# main.net
KiCad netlist of a schematic drawn in Altium Designer
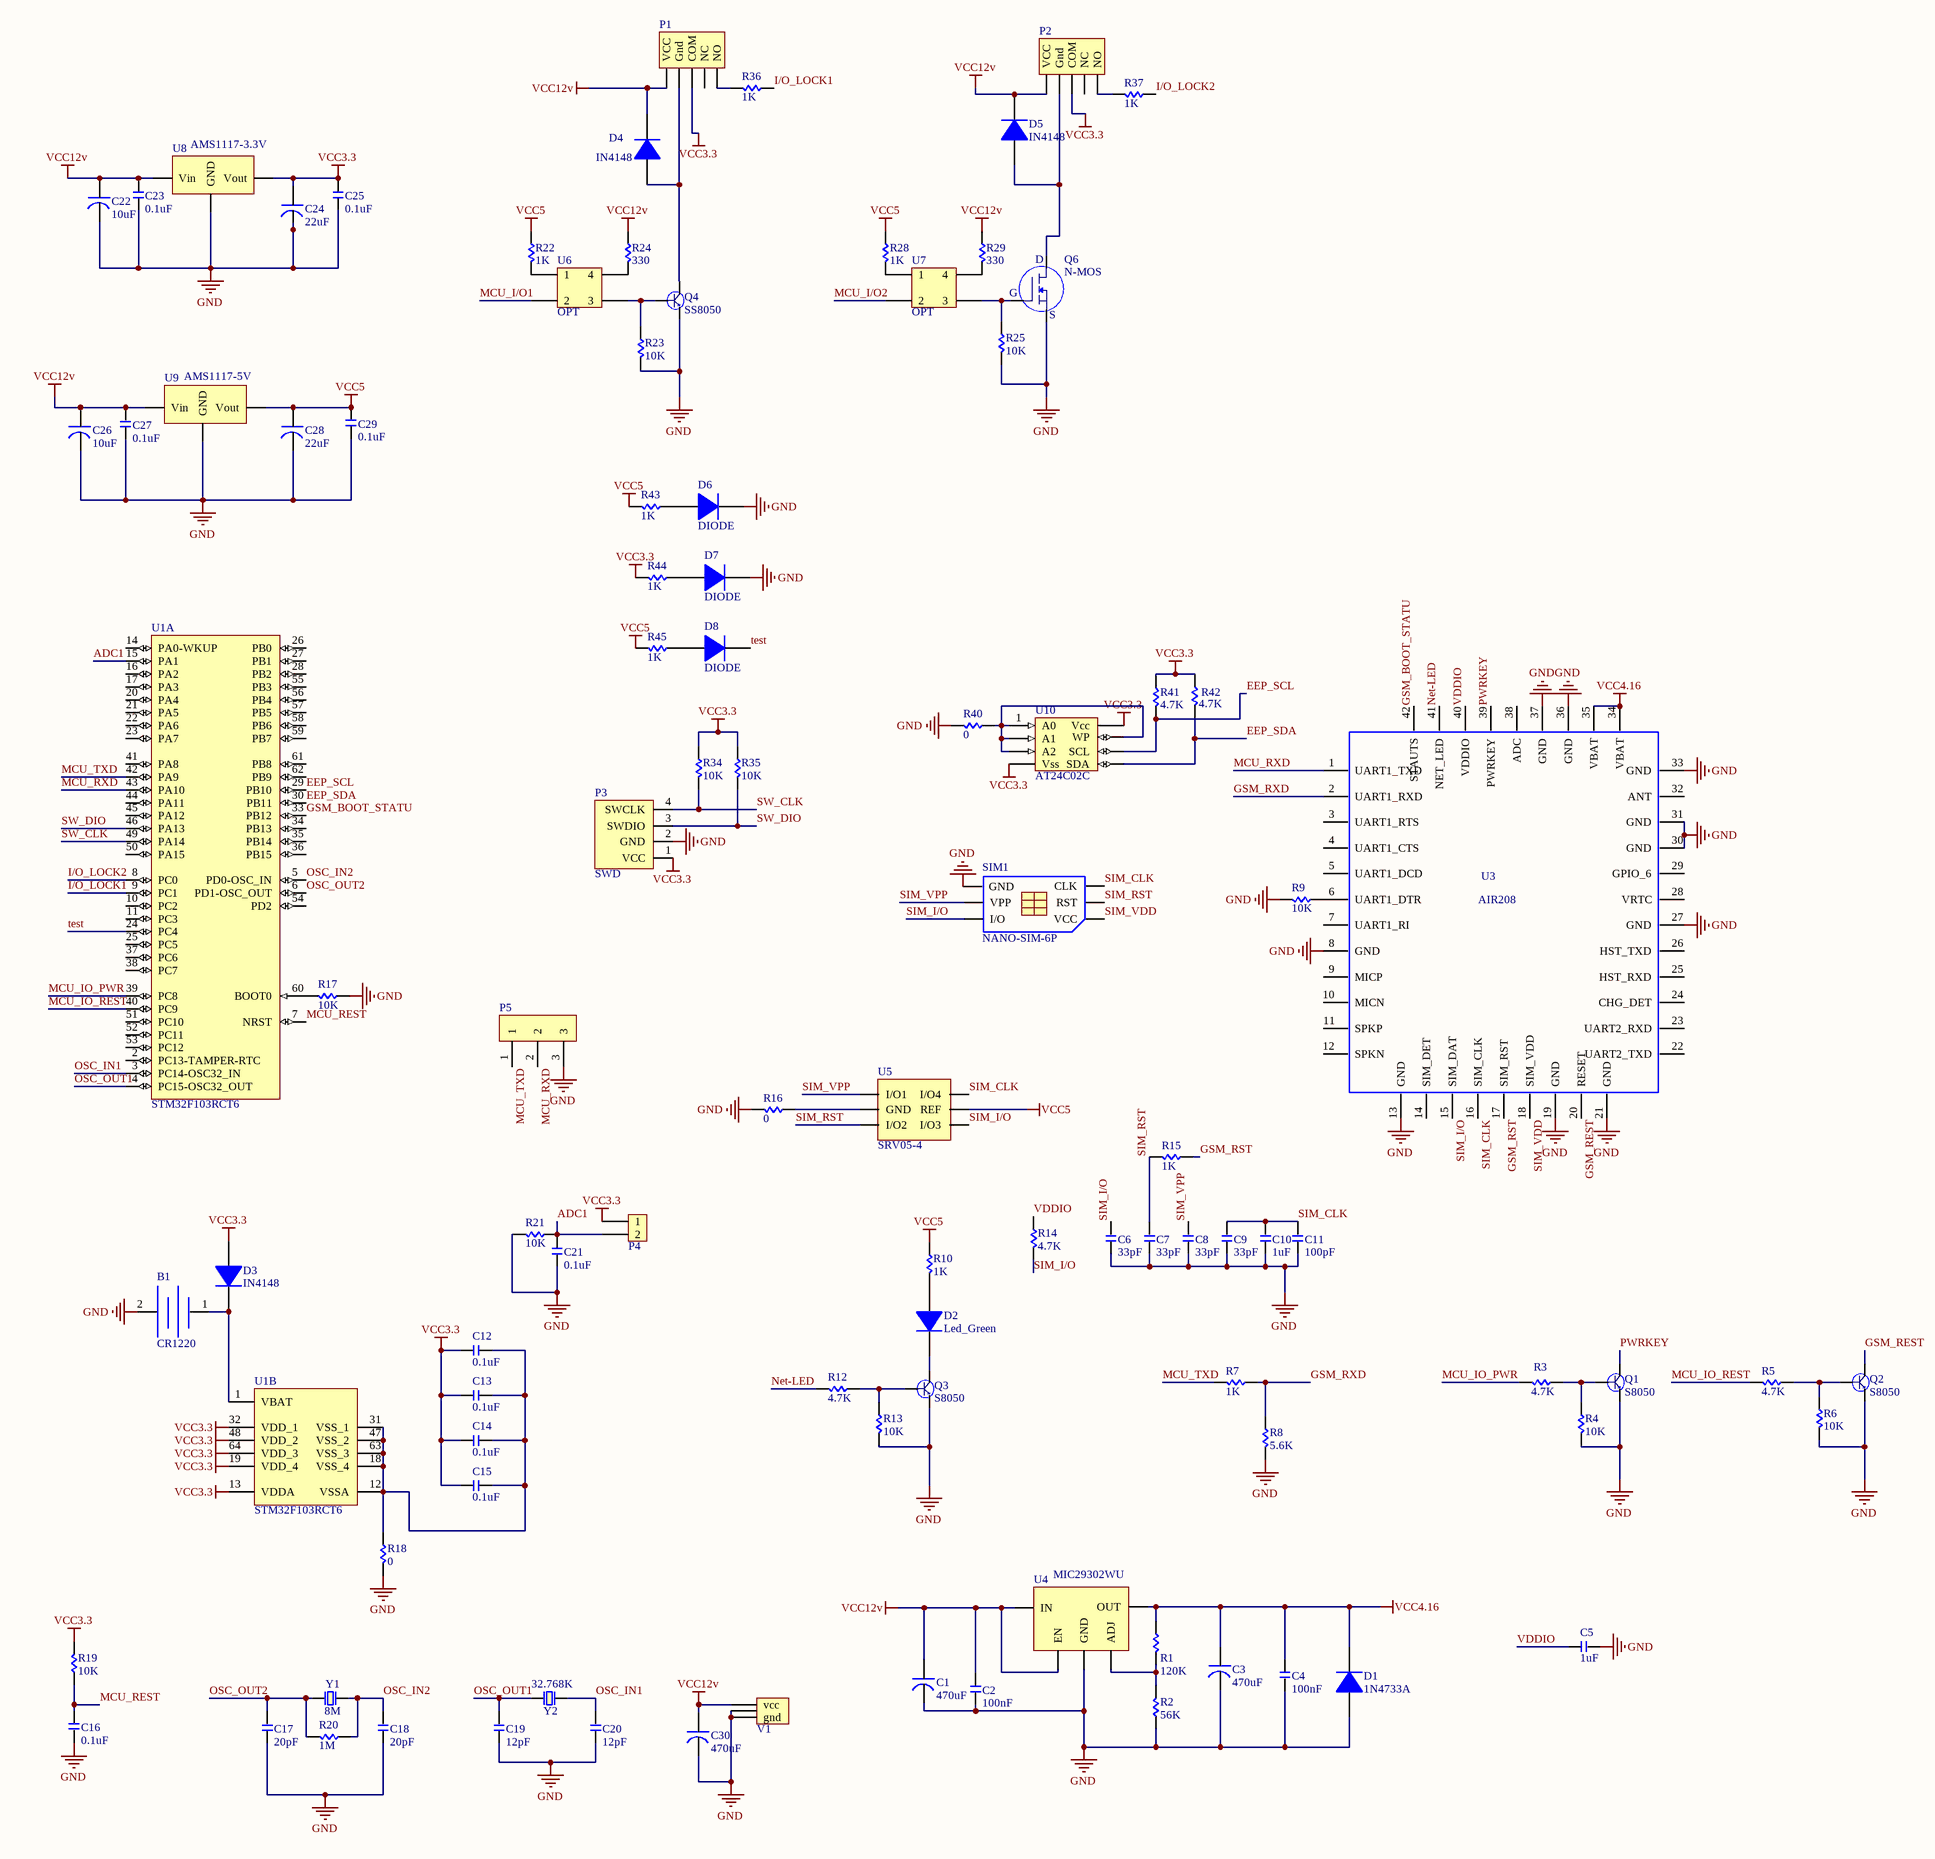
[diagram p0: main.SchDoc]

(export (version "E")
  (design (tool "Eeschema 10.0.6"))
  (components
    (comp (ref "B1") (value "CR1220") (footprint "CR1220") (libsource (lib "dev") (part "BAT")))
    (comp (ref "C1") (value "470uF") (footprint "10mmx10mm+") (libsource (lib "dev") (part "Cap_Elec")))
    (comp (ref "C2") (value "100nF") (footprint "0805") (libsource (lib "dev") (part "Cap")))
    (comp (ref "C3") (value "470uF") (footprint "10mmx10mm+") (libsource (lib "dev") (part "Cap_Elec")))
    (comp (ref "C4") (value "100nF") (footprint "0805") (libsource (lib "dev") (part "Cap")))
    (comp (ref "C5") (value "1uF") (footprint "0805") (libsource (lib "dev") (part "Cap")))
    (comp (ref "C6") (value "33pF") (footprint "0805") (libsource (lib "dev") (part "Cap")))
    (comp (ref "C7") (value "33pF") (footprint "0805") (libsource (lib "dev") (part "Cap")))
    (comp (ref "C8") (value "33pF") (footprint "0805") (libsource (lib "dev") (part "Cap")))
    (comp (ref "C9") (value "33pF") (footprint "0805") (libsource (lib "dev") (part "Cap")))
    (comp (ref "C10") (value "1uF") (footprint "0805") (libsource (lib "dev") (part "Cap")))
    (comp (ref "C11") (value "100pF") (footprint "0805") (libsource (lib "dev") (part "Cap")))
    (comp (ref "C12") (value "0.1uF") (footprint "0805") (libsource (lib "dev") (part "Cap")))
    (comp (ref "C13") (value "0.1uF") (footprint "0805") (libsource (lib "dev") (part "Cap")))
    (comp (ref "C14") (value "0.1uF") (footprint "0805") (libsource (lib "dev") (part "Cap")))
    (comp (ref "C15") (value "0.1uF") (footprint "0805") (libsource (lib "dev") (part "Cap")))
    (comp (ref "C16") (value "0.1uF") (footprint "0805") (libsource (lib "dev") (part "Cap")))
    (comp (ref "C17") (value "20pF") (footprint "0805") (libsource (lib "dev") (part "Cap")))
    (comp (ref "C18") (value "20pF") (footprint "0805") (libsource (lib "dev") (part "Cap")))
    (comp (ref "C19") (value "12pF") (footprint "0805") (libsource (lib "dev") (part "Cap")))
    (comp (ref "C20") (value "12pF") (footprint "0805") (libsource (lib "dev") (part "Cap")))
    (comp (ref "C21") (value "0.1uF") (footprint "0805") (libsource (lib "dev") (part "Cap")))
    (comp (ref "C22") (value "10uF") (footprint "1206") (libsource (lib "dev") (part "Cap_Elec")))
    (comp (ref "C23") (value "0.1uF") (footprint "0805") (libsource (lib "dev") (part "Cap")))
    (comp (ref "C24") (value "22uF") (footprint "1206") (libsource (lib "dev") (part "Cap_Elec")))
    (comp (ref "C25") (value "0.1uF") (footprint "0805") (libsource (lib "dev") (part "Cap")))
    (comp (ref "C26") (value "10uF") (footprint "1206") (libsource (lib "dev") (part "Cap_Elec")))
    (comp (ref "C27") (value "0.1uF") (footprint "0805") (libsource (lib "dev") (part "Cap")))
    (comp (ref "C28") (value "22uF") (footprint "1206") (libsource (lib "dev") (part "Cap_Elec")))
    (comp (ref "C29") (value "0.1uF") (footprint "0805") (libsource (lib "dev") (part "Cap")))
    (comp (ref "C30") (value "470uF") (footprint "DIP2_8.3x3.1") (libsource (lib "dev") (part "Cap_Elec")))
    (comp (ref "D1") (value "1N4733A") (footprint "Dip-6mm") (libsource (lib "dev") (part "DIODE")))
    (comp (ref "D2") (value "Led_Green") (footprint "0603") (libsource (lib "dev") (part "DIODE")))
    (comp (ref "D3") (value "IN4148") (footprint "1206") (libsource (lib "dev") (part "DIODE")))
    (comp (ref "D4") (value "IN4148") (footprint "1206") (libsource (lib "dev") (part "DIODE")))
    (comp (ref "D5") (value "IN4148") (footprint "1206") (libsource (lib "dev") (part "DIODE")))
    (comp (ref "D6") (value "DIODE") (footprint "0603") (libsource (lib "dev") (part "DIODE")))
    (comp (ref "D7") (value "DIODE") (footprint "0603") (libsource (lib "dev") (part "DIODE")))
    (comp (ref "D8") (value "DIODE") (footprint "0603") (libsource (lib "dev") (part "DIODE")))
    (comp (ref "P1") (value "Ele_lock_Pin") (footprint "Pin5") (libsource (lib "dev") (part "Ele_lock_Pin")))
    (comp (ref "P2") (value "Ele_lock_Pin") (footprint "Pin5") (libsource (lib "dev") (part "Ele_lock_Pin")))
    (comp (ref "P3") (value "SWD") (footprint "PIN4") (libsource (lib "dev") (part "SWD")))
    (comp (ref "P4") (value "Pin2") (footprint "XH2.54_2") (libsource (lib "dev") (part "Pin2")))
    (comp (ref "P5") (value "pin3") (footprint "PIN3") (libsource (lib "dev") (part "pin3")))
    (comp (ref "Q1") (value "S8050") (footprint "sot-23") (libsource (lib "dev") (part "Npn-Sot-23")))
    (comp (ref "Q2") (value "S8050") (footprint "sot-23") (libsource (lib "dev") (part "Npn-Sot-23")))
    (comp (ref "Q3") (value "S8050") (footprint "sot-23") (libsource (lib "dev") (part "Npn-Sot-23")))
    (comp (ref "Q4") (value "SS8050") (footprint "sot-23") (libsource (lib "dev") (part "Npn-Sot-23")))
    (comp (ref "Q6") (value "N-MOS") (footprint "SOT-23-3") (libsource (lib "dev") (part "N-MOS")))
    (comp (ref "R1") (value "120K") (footprint "0805") (libsource (lib "dev") (part "Res")))
    (comp (ref "R2") (value "56K") (footprint "0805") (libsource (lib "dev") (part "Res")))
    (comp (ref "R3") (value "4.7K") (footprint "0805") (libsource (lib "dev") (part "Res")))
    (comp (ref "R4") (value "10K") (footprint "0805") (libsource (lib "dev") (part "Res")))
    (comp (ref "R5") (value "4.7K") (footprint "0805") (libsource (lib "dev") (part "Res")))
    (comp (ref "R6") (value "10K") (footprint "0805") (libsource (lib "dev") (part "Res")))
    (comp (ref "R7") (value "1K") (footprint "0805") (libsource (lib "dev") (part "Res")))
    (comp (ref "R8") (value "5.6K") (footprint "0805") (libsource (lib "dev") (part "Res")))
    (comp (ref "R9") (value "10K") (footprint "0805") (libsource (lib "dev") (part "Res")))
    (comp (ref "R10") (value "1K") (footprint "0805") (libsource (lib "dev") (part "Res")))
    (comp (ref "R12") (value "4.7K") (footprint "0805") (libsource (lib "dev") (part "Res")))
    (comp (ref "R13") (value "10K") (footprint "0805") (libsource (lib "dev") (part "Res")))
    (comp (ref "R14") (value "4.7K") (footprint "0805") (libsource (lib "dev") (part "Res")))
    (comp (ref "R15") (value "1K") (footprint "0805") (libsource (lib "dev") (part "Res")))
    (comp (ref "R16") (value "0") (footprint "0603") (libsource (lib "dev") (part "Res")))
    (comp (ref "R17") (value "10K") (footprint "0805") (libsource (lib "dev") (part "Res")))
    (comp (ref "R18") (value "0") (footprint "0603") (libsource (lib "dev") (part "Res")))
    (comp (ref "R19") (value "10K") (footprint "0805") (libsource (lib "dev") (part "Res")))
    (comp (ref "R20") (value "1M") (footprint "0805") (libsource (lib "dev") (part "Res")))
    (comp (ref "R21") (value "10K") (footprint "0805") (libsource (lib "dev") (part "Res")))
    (comp (ref "R22") (value "1K") (footprint "0805") (libsource (lib "dev") (part "Res")))
    (comp (ref "R23") (value "10K") (footprint "0805") (libsource (lib "dev") (part "Res")))
    (comp (ref "R24") (value "330") (footprint "0805") (libsource (lib "dev") (part "Res")))
    (comp (ref "R25") (value "10K") (footprint "0805") (libsource (lib "dev") (part "Res")))
    (comp (ref "R28") (value "1K") (footprint "0805") (libsource (lib "dev") (part "Res")))
    (comp (ref "R29") (value "330") (footprint "0805") (libsource (lib "dev") (part "Res")))
    (comp (ref "R34") (value "10K") (footprint "0805") (libsource (lib "dev") (part "Res")))
    (comp (ref "R35") (value "10K") (footprint "0805") (libsource (lib "dev") (part "Res")))
    (comp (ref "R36") (value "1K") (footprint "0805") (libsource (lib "dev") (part "Res")))
    (comp (ref "R37") (value "1K") (footprint "0805") (libsource (lib "dev") (part "Res")))
    (comp (ref "R40") (value "0") (footprint "0603") (libsource (lib "dev") (part "Res")))
    (comp (ref "R41") (value "4.7K") (footprint "0603") (libsource (lib "dev") (part "Res")))
    (comp (ref "R42") (value "4.7K") (footprint "0603") (libsource (lib "dev") (part "Res")))
    (comp (ref "R43") (value "1K") (footprint "0603") (libsource (lib "dev") (part "Res")))
    (comp (ref "R44") (value "1K") (footprint "0603") (libsource (lib "dev") (part "Res")))
    (comp (ref "R45") (value "1K") (footprint "0603") (libsource (lib "dev") (part "Res")))
    (comp (ref "SIM1")
      (value "NANO-SIM-6P")
      (footprint "NANO-SIM-6P")
      (libsource (lib "dev") (part "NANO-SIM-6P"))
    )
    (comp (ref "U1")
      (value "STM32F103RCT6")
      (footprint "STM-LQFP64_M")
      (libsource (lib "STMicroelectronics STM32 F1") (part "STM32F103RCT6"))
    )
    (comp (ref "U3") (value "AIR208") (footprint "Air208") (libsource (lib "AIR208") (part "AIR208")))
    (comp (ref "U4") (value "MIC29302WU") (footprint "TO-263-5") (libsource (lib "dev") (part "MIC29302WU")))
    (comp (ref "U5") (value "SRV05-4") (footprint "Sot-23-6") (libsource (lib "dev") (part "SRV05-4")))
    (comp (ref "U6") (value "OPT") (footprint "SOP4") (libsource (lib "dev") (part "OPT")))
    (comp (ref "U7") (value "OPT") (footprint "SOP4") (libsource (lib "dev") (part "OPT")))
    (comp (ref "U8")
      (value "AMS1117-3.3V")
      (footprint "SOT-223")
      (libsource (lib "dev") (part "AMS1117-3.3V"))
    )
    (comp (ref "U9") (value "AMS1117-5V") (footprint "SOT-223") (libsource (lib "dev") (part "AMS1117-3.3V")))
    (comp (ref "U10") (value "AT24C02C") (footprint "SOP8") (libsource (lib "dev") (part "AT24C02C")))
    (comp (ref "V1")
      (value "POWER_PIN")
      (footprint "POWER_PIN_PCB")
      (libsource (lib "dev") (part "POWER_PIN"))
    )
    (comp (ref "Y1") (value "8M") (footprint "crystal") (libsource (lib "dev") (part "crystal")))
    (comp (ref "Y2") (value "32.768K") (footprint "PIN1.1") (libsource (lib "dev") (part "crystal")))
  )
  (nets
    (net (code "1") (name "/ADC1") (class "Default")
      (node (ref "C21") (pin "2") (pinfunction "2_2") (pintype "passive"))
      (node (ref "P4") (pin "2") (pinfunction "2_2") (pintype "passive"))
      (node (ref "R21") (pin "2") (pinfunction "2_2") (pintype "passive"))
      (node (ref "U1") (pin "15") (pinfunction "PA1_15") (pintype "bidirectional"))
    )
    (net (code "2") (name "/EEP_SCL") (class "Default")
      (node (ref "R41") (pin "1") (pinfunction "1_1") (pintype "passive"))
      (node (ref "U1") (pin "29") (pinfunction "PB10_29") (pintype "bidirectional"))
      (node (ref "U10") (pin "6") (pinfunction "SCL_6") (pintype "bidirectional"))
    )
    (net (code "3") (name "/EEP_SDA") (class "Default")
      (node (ref "R42") (pin "1") (pinfunction "1_1") (pintype "passive"))
      (node (ref "U1") (pin "30") (pinfunction "PB11_30") (pintype "bidirectional"))
      (node (ref "U10") (pin "5") (pinfunction "SDA_5") (pintype "bidirectional"))
    )
    (net (code "4") (name "/GSM_BOOT_STATU") (class "Default")
      (node (ref "U1") (pin "33") (pinfunction "PB12_33") (pintype "bidirectional"))
      (node (ref "U3") (pin "42") (pinfunction "STAUTS_42") (pintype "passive"))
    )
    (net (code "5") (name "/GSM_REST") (class "Default")
      (node (ref "Q2") (pin "3") (pinfunction "3_3") (pintype "passive"))
      (node (ref "U3") (pin "20") (pinfunction "RESET_20") (pintype "passive"))
    )
    (net (code "6") (name "/GSM_RST") (class "Default")
      (node (ref "R15") (pin "2") (pinfunction "2_2") (pintype "passive"))
      (node (ref "U3") (pin "17") (pinfunction "SIM_RST_17") (pintype "passive"))
    )
    (net (code "7") (name "/GSM_RXD") (class "Default")
      (node (ref "R7") (pin "2") (pinfunction "2_2") (pintype "passive"))
      (node (ref "R8") (pin "2") (pinfunction "2_2") (pintype "passive"))
      (node (ref "U3") (pin "2") (pinfunction "UART1_RXD_2") (pintype "passive"))
    )
    (net (code "8") (name "/I{slash}O_LOCK1") (class "Default")
      (node (ref "R36") (pin "2") (pinfunction "2_2") (pintype "passive"))
      (node (ref "U1") (pin "9") (pinfunction "PC1_9") (pintype "bidirectional"))
    )
    (net (code "9") (name "/I{slash}O_LOCK2") (class "Default")
      (node (ref "R37") (pin "2") (pinfunction "2_2") (pintype "passive"))
      (node (ref "U1") (pin "8") (pinfunction "PC0_8") (pintype "bidirectional"))
    )
    (net (code "10") (name "/MCU_IO_PWR") (class "Default")
      (node (ref "R3") (pin "1") (pinfunction "1_1") (pintype "passive"))
      (node (ref "U1") (pin "39") (pinfunction "PC8_39") (pintype "bidirectional"))
    )
    (net (code "11") (name "/MCU_IO_REST") (class "Default")
      (node (ref "R5") (pin "1") (pinfunction "1_1") (pintype "passive"))
      (node (ref "U1") (pin "40") (pinfunction "PC9_40") (pintype "bidirectional"))
    )
    (net (code "12") (name "/MCU_I{slash}O1") (class "Default")
      (node (ref "U6") (pin "2") (pinfunction "2_2") (pintype "passive"))
    )
    (net (code "13") (name "/MCU_I{slash}O2") (class "Default")
      (node (ref "U7") (pin "2") (pinfunction "2_2") (pintype "passive"))
    )
    (net (code "14") (name "/MCU_REST") (class "Default")
      (node (ref "C16") (pin "1") (pinfunction "1_1") (pintype "passive"))
      (node (ref "R19") (pin "2") (pinfunction "2_2") (pintype "passive"))
      (node (ref "U1") (pin "7") (pinfunction "NRST_7") (pintype "bidirectional"))
    )
    (net (code "15") (name "/MCU_RXD") (class "Default")
      (node (ref "P5") (pin "2") (pinfunction "2_2") (pintype "passive"))
      (node (ref "U1") (pin "43") (pinfunction "PA10_43") (pintype "bidirectional"))
      (node (ref "U3") (pin "1") (pinfunction "UART1_TXD_1") (pintype "passive"))
    )
    (net (code "16") (name "/MCU_TXD") (class "Default")
      (node (ref "P5") (pin "1") (pinfunction "1_1") (pintype "passive"))
      (node (ref "R7") (pin "1") (pinfunction "1_1") (pintype "passive"))
      (node (ref "U1") (pin "42") (pinfunction "PA9_42") (pintype "bidirectional"))
    )
    (net (code "17") (name "/Net-LED") (class "Default")
      (node (ref "R12") (pin "1") (pinfunction "1_1") (pintype "passive"))
      (node (ref "U3") (pin "41") (pinfunction "NET_LED_41") (pintype "passive"))
    )
    (net (code "18") (name "/OSC_IN1") (class "Default")
      (node (ref "C20") (pin "2") (pinfunction "2_2") (pintype "passive"))
      (node (ref "U1") (pin "3") (pinfunction "PC14-OSC32_IN_3") (pintype "bidirectional"))
      (node (ref "Y2") (pin "2") (pinfunction "2_2") (pintype "passive"))
    )
    (net (code "19") (name "/OSC_IN2") (class "Default")
      (node (ref "C18") (pin "2") (pinfunction "2_2") (pintype "passive"))
      (node (ref "R20") (pin "2") (pinfunction "2_2") (pintype "passive"))
      (node (ref "U1") (pin "5") (pinfunction "PD0-OSC_IN_5") (pintype "bidirectional"))
      (node (ref "Y1") (pin "2") (pinfunction "2_2") (pintype "passive"))
    )
    (net (code "20") (name "/OSC_OUT1") (class "Default")
      (node (ref "C19") (pin "2") (pinfunction "2_2") (pintype "passive"))
      (node (ref "U1") (pin "4") (pinfunction "PC15-OSC32_OUT_4") (pintype "bidirectional"))
      (node (ref "Y2") (pin "1") (pinfunction "1_1") (pintype "passive"))
    )
    (net (code "21") (name "/OSC_OUT2") (class "Default")
      (node (ref "C17") (pin "2") (pinfunction "2_2") (pintype "passive"))
      (node (ref "R20") (pin "1") (pinfunction "1_1") (pintype "passive"))
      (node (ref "U1") (pin "6") (pinfunction "PD1-OSC_OUT_6") (pintype "bidirectional"))
      (node (ref "Y1") (pin "1") (pinfunction "1_1") (pintype "passive"))
    )
    (net (code "22") (name "/PWRKEY") (class "Default")
      (node (ref "Q1") (pin "3") (pinfunction "3_3") (pintype "passive"))
      (node (ref "U3") (pin "39") (pinfunction "PWRKEY_39") (pintype "passive"))
    )
    (net (code "23") (name "/SIM_CLK") (class "Default")
      (node (ref "C10") (pin "2") (pinfunction "2_2") (pintype "passive"))
      (node (ref "C11") (pin "2") (pinfunction "2_2") (pintype "passive"))
      (node (ref "C9") (pin "2") (pinfunction "2_2") (pintype "passive"))
      (node (ref "SIM1") (pin "3") (pinfunction "CLK_3") (pintype "passive"))
      (node (ref "U3") (pin "16") (pinfunction "SIM_CLK_16") (pintype "passive"))
      (node (ref "U5") (pin "6") (pinfunction "I/O4_6") (pintype "passive"))
    )
    (net (code "24") (name "/SIM_I{slash}O") (class "Default")
      (node (ref "C6") (pin "2") (pinfunction "2_2") (pintype "passive"))
      (node (ref "R14") (pin "1") (pinfunction "1_1") (pintype "passive"))
      (node (ref "SIM1") (pin "7") (pinfunction "I/O_7") (pintype "passive"))
      (node (ref "U3") (pin "15") (pinfunction "SIM_DAT_15") (pintype "passive"))
      (node (ref "U5") (pin "4") (pinfunction "I/O3_4") (pintype "passive"))
    )
    (net (code "25") (name "/SIM_RST") (class "Default")
      (node (ref "C7") (pin "2") (pinfunction "2_2") (pintype "passive"))
      (node (ref "R15") (pin "1") (pinfunction "1_1") (pintype "passive"))
      (node (ref "SIM1") (pin "2") (pinfunction "RST_2") (pintype "passive"))
      (node (ref "U5") (pin "3") (pinfunction "I/O2_3") (pintype "passive"))
    )
    (net (code "26") (name "/SIM_VDD") (class "Default")
      (node (ref "SIM1") (pin "1") (pinfunction "VCC_1") (pintype "passive"))
      (node (ref "U3") (pin "18") (pinfunction "SIM_VDD_18") (pintype "passive"))
    )
    (net (code "27") (name "/SIM_VPP") (class "Default")
      (node (ref "C8") (pin "2") (pinfunction "2_2") (pintype "passive"))
      (node (ref "SIM1") (pin "6") (pinfunction "VPP_6") (pintype "passive"))
      (node (ref "U5") (pin "1") (pinfunction "I/O1_1") (pintype "passive"))
    )
    (net (code "28") (name "/SW_CLK") (class "Default")
      (node (ref "P3") (pin "4") (pinfunction "SWCLK_4") (pintype "passive"))
      (node (ref "R34") (pin "1") (pinfunction "1_1") (pintype "passive"))
      (node (ref "U1") (pin "49") (pinfunction "PA14_49") (pintype "bidirectional"))
    )
    (net (code "29") (name "/SW_DIO") (class "Default")
      (node (ref "P3") (pin "3") (pinfunction "SWDIO_3") (pintype "passive"))
      (node (ref "R35") (pin "1") (pinfunction "1_1") (pintype "passive"))
      (node (ref "U1") (pin "46") (pinfunction "PA13_46") (pintype "bidirectional"))
    )
    (net (code "30") (name "/VDDIO") (class "Default")
      (node (ref "C5") (pin "1") (pinfunction "1_1") (pintype "passive"))
      (node (ref "R14") (pin "2") (pinfunction "2_2") (pintype "passive"))
      (node (ref "U3") (pin "40") (pinfunction "VDDIO_40") (pintype "passive"))
    )
    (net (code "31") (name "/test") (class "Default")
      (node (ref "D8") (pin "2") (pinfunction "2_2") (pintype "passive"))
      (node (ref "U1") (pin "24") (pinfunction "PC4_24") (pintype "bidirectional"))
    )
    (net (code "32") (name "GND") (class "Default")
      (node (ref "B1") (pin "2") (pinfunction "2_2") (pintype "passive"))
      (node (ref "C1") (pin "2") (pinfunction "2_2") (pintype "passive"))
      (node (ref "C10") (pin "1") (pinfunction "1_1") (pintype "passive"))
      (node (ref "C11") (pin "1") (pinfunction "1_1") (pintype "passive"))
      (node (ref "C16") (pin "2") (pinfunction "2_2") (pintype "passive"))
      (node (ref "C17") (pin "1") (pinfunction "1_1") (pintype "passive"))
      (node (ref "C18") (pin "1") (pinfunction "1_1") (pintype "passive"))
      (node (ref "C19") (pin "1") (pinfunction "1_1") (pintype "passive"))
      (node (ref "C2") (pin "1") (pinfunction "1_1") (pintype "passive"))
      (node (ref "C20") (pin "1") (pinfunction "1_1") (pintype "passive"))
      (node (ref "C21") (pin "1") (pinfunction "1_1") (pintype "passive"))
      (node (ref "C22") (pin "2") (pinfunction "2_2") (pintype "passive"))
      (node (ref "C23") (pin "1") (pinfunction "1_1") (pintype "passive"))
      (node (ref "C24") (pin "2") (pinfunction "2_2") (pintype "passive"))
      (node (ref "C25") (pin "1") (pinfunction "1_1") (pintype "passive"))
      (node (ref "C26") (pin "2") (pinfunction "2_2") (pintype "passive"))
      (node (ref "C27") (pin "1") (pinfunction "1_1") (pintype "passive"))
      (node (ref "C28") (pin "2") (pinfunction "2_2") (pintype "passive"))
      (node (ref "C29") (pin "2") (pinfunction "2_2") (pintype "passive"))
      (node (ref "C3") (pin "2") (pinfunction "2_2") (pintype "passive"))
      (node (ref "C30") (pin "2") (pinfunction "2_2") (pintype "passive"))
      (node (ref "C4") (pin "2") (pinfunction "2_2") (pintype "passive"))
      (node (ref "C5") (pin "2") (pinfunction "2_2") (pintype "passive"))
      (node (ref "C6") (pin "1") (pinfunction "1_1") (pintype "passive"))
      (node (ref "C7") (pin "1") (pinfunction "1_1") (pintype "passive"))
      (node (ref "C8") (pin "1") (pinfunction "1_1") (pintype "passive"))
      (node (ref "C9") (pin "1") (pinfunction "1_1") (pintype "passive"))
      (node (ref "D1") (pin "1") (pinfunction "1_1") (pintype "passive"))
      (node (ref "D6") (pin "2") (pinfunction "2_2") (pintype "passive"))
      (node (ref "D7") (pin "2") (pinfunction "2_2") (pintype "passive"))
      (node (ref "P3") (pin "2") (pinfunction "GND_2") (pintype "passive"))
      (node (ref "P5") (pin "3") (pinfunction "3_3") (pintype "passive"))
      (node (ref "Q1") (pin "2") (pinfunction "2_2") (pintype "passive"))
      (node (ref "Q2") (pin "2") (pinfunction "2_2") (pintype "passive"))
      (node (ref "Q3") (pin "2") (pinfunction "2_2") (pintype "passive"))
      (node (ref "Q4") (pin "2") (pinfunction "2_2") (pintype "passive"))
      (node (ref "Q6") (pin "2") (pinfunction "S_2") (pintype "passive"))
      (node (ref "R13") (pin "1") (pinfunction "1_1") (pintype "passive"))
      (node (ref "R16") (pin "1") (pinfunction "1_1") (pintype "passive"))
      (node (ref "R17") (pin "2") (pinfunction "2_2") (pintype "passive"))
      (node (ref "R18") (pin "1") (pinfunction "1_1") (pintype "passive"))
      (node (ref "R2") (pin "2") (pinfunction "2_2") (pintype "passive"))
      (node (ref "R21") (pin "1") (pinfunction "1_1") (pintype "passive"))
      (node (ref "R23") (pin "1") (pinfunction "1_1") (pintype "passive"))
      (node (ref "R25") (pin "1") (pinfunction "1_1") (pintype "passive"))
      (node (ref "R4") (pin "1") (pinfunction "1_1") (pintype "passive"))
      (node (ref "R40") (pin "1") (pinfunction "1_1") (pintype "passive"))
      (node (ref "R6") (pin "1") (pinfunction "1_1") (pintype "passive"))
      (node (ref "R8") (pin "1") (pinfunction "1_1") (pintype "passive"))
      (node (ref "R9") (pin "1") (pinfunction "1_1") (pintype "passive"))
      (node (ref "SIM1") (pin "5") (pinfunction "GND_5") (pintype "passive"))
      (node (ref "U3") (pin "13") (pinfunction "GND_13") (pintype "passive"))
      (node (ref "U3") (pin "19") (pinfunction "GND_19") (pintype "passive"))
      (node (ref "U3") (pin "21") (pinfunction "GND_21") (pintype "passive"))
      (node (ref "U3") (pin "27") (pinfunction "GND_27") (pintype "passive"))
      (node (ref "U3") (pin "30") (pinfunction "GND_30") (pintype "passive"))
      (node (ref "U3") (pin "31") (pinfunction "GND_31") (pintype "passive"))
      (node (ref "U3") (pin "33") (pinfunction "GND_33") (pintype "passive"))
      (node (ref "U3") (pin "36") (pinfunction "GND_36") (pintype "passive"))
      (node (ref "U3") (pin "37") (pinfunction "GND_37") (pintype "passive"))
      (node (ref "U3") (pin "8") (pinfunction "GND_8") (pintype "passive"))
      (node (ref "U4") (pin "3") (pinfunction "GND_3") (pintype "passive"))
      (node (ref "U8") (pin "1") (pinfunction "GND_1") (pintype "power_in"))
      (node (ref "U9") (pin "1") (pinfunction "GND_1") (pintype "power_in"))
      (node (ref "V1") (pin "2") (pinfunction "gnd_2") (pintype "passive"))
      (node (ref "V1") (pin "3") (pinfunction "3_3") (pintype "passive"))
    )
    (net (code "33") (name "Net-(B1-VCC)") (class "Default")
      (node (ref "B1") (pin "1") (pinfunction "VCC_1") (pintype "passive"))
      (node (ref "D3") (pin "2") (pinfunction "2_2") (pintype "passive"))
      (node (ref "U1") (pin "1") (pinfunction "VBAT_1") (pintype "power_in"))
    )
    (net (code "34") (name "Net-(D2-Pad1)") (class "Default")
      (node (ref "D2") (pin "1") (pinfunction "1_1") (pintype "passive"))
      (node (ref "R10") (pin "1") (pinfunction "1_1") (pintype "passive"))
    )
    (net (code "35") (name "Net-(D2-Pad2)") (class "Default")
      (node (ref "D2") (pin "2") (pinfunction "2_2") (pintype "passive"))
      (node (ref "Q3") (pin "3") (pinfunction "3_3") (pintype "passive"))
    )
    (net (code "36") (name "Net-(D6-Pad1)") (class "Default")
      (node (ref "D6") (pin "1") (pinfunction "1_1") (pintype "passive"))
      (node (ref "R43") (pin "2") (pinfunction "2_2") (pintype "passive"))
    )
    (net (code "37") (name "Net-(D7-Pad1)") (class "Default")
      (node (ref "D7") (pin "1") (pinfunction "1_1") (pintype "passive"))
      (node (ref "R44") (pin "2") (pinfunction "2_2") (pintype "passive"))
    )
    (net (code "38") (name "Net-(D8-Pad1)") (class "Default")
      (node (ref "D8") (pin "1") (pinfunction "1_1") (pintype "passive"))
      (node (ref "R45") (pin "2") (pinfunction "2_2") (pintype "passive"))
    )
    (net (code "39") (name "Net-(P1-Gnd)") (class "Default")
      (node (ref "D4") (pin "1") (pinfunction "1_1") (pintype "passive"))
      (node (ref "P1") (pin "2") (pinfunction "Gnd_2") (pintype "passive"))
      (node (ref "Q4") (pin "3") (pinfunction "3_3") (pintype "passive"))
    )
    (net (code "40") (name "Net-(P1-NO)") (class "Default")
      (node (ref "P1") (pin "5") (pinfunction "NO_5") (pintype "passive"))
      (node (ref "R36") (pin "1") (pinfunction "1_1") (pintype "passive"))
    )
    (net (code "41") (name "Net-(P2-Gnd)") (class "Default")
      (node (ref "D5") (pin "1") (pinfunction "1_1") (pintype "passive"))
      (node (ref "P2") (pin "2") (pinfunction "Gnd_2") (pintype "passive"))
      (node (ref "Q6") (pin "3") (pinfunction "D_3") (pintype "passive"))
    )
    (net (code "42") (name "Net-(P2-NO)") (class "Default")
      (node (ref "P2") (pin "5") (pinfunction "NO_5") (pintype "passive"))
      (node (ref "R37") (pin "1") (pinfunction "1_1") (pintype "passive"))
    )
    (net (code "43") (name "Net-(Q1-Pad1)") (class "Default")
      (node (ref "Q1") (pin "1") (pinfunction "1_1") (pintype "passive"))
      (node (ref "R3") (pin "2") (pinfunction "2_2") (pintype "passive"))
      (node (ref "R4") (pin "2") (pinfunction "2_2") (pintype "passive"))
    )
    (net (code "44") (name "Net-(Q2-Pad1)") (class "Default")
      (node (ref "Q2") (pin "1") (pinfunction "1_1") (pintype "passive"))
      (node (ref "R5") (pin "2") (pinfunction "2_2") (pintype "passive"))
      (node (ref "R6") (pin "2") (pinfunction "2_2") (pintype "passive"))
    )
    (net (code "45") (name "Net-(Q3-Pad1)") (class "Default")
      (node (ref "Q3") (pin "1") (pinfunction "1_1") (pintype "passive"))
      (node (ref "R12") (pin "2") (pinfunction "2_2") (pintype "passive"))
      (node (ref "R13") (pin "2") (pinfunction "2_2") (pintype "passive"))
    )
    (net (code "46") (name "Net-(Q4-Pad1)") (class "Default")
      (node (ref "Q4") (pin "1") (pinfunction "1_1") (pintype "passive"))
      (node (ref "R23") (pin "2") (pinfunction "2_2") (pintype "passive"))
      (node (ref "U6") (pin "3") (pinfunction "3_3") (pintype "passive"))
    )
    (net (code "47") (name "Net-(Q6-G)") (class "Default")
      (node (ref "Q6") (pin "1") (pinfunction "G_1") (pintype "passive"))
      (node (ref "R25") (pin "2") (pinfunction "2_2") (pintype "passive"))
      (node (ref "U7") (pin "3") (pinfunction "3_3") (pintype "passive"))
    )
    (net (code "48") (name "Net-(R22-Pad1)") (class "Default")
      (node (ref "R22") (pin "1") (pinfunction "1_1") (pintype "passive"))
      (node (ref "U6") (pin "1") (pinfunction "1_1") (pintype "passive"))
    )
    (net (code "49") (name "Net-(R24-Pad1)") (class "Default")
      (node (ref "R24") (pin "1") (pinfunction "1_1") (pintype "passive"))
      (node (ref "U6") (pin "4") (pinfunction "4_4") (pintype "passive"))
    )
    (net (code "50") (name "Net-(R28-Pad1)") (class "Default")
      (node (ref "R28") (pin "1") (pinfunction "1_1") (pintype "passive"))
      (node (ref "U7") (pin "1") (pinfunction "1_1") (pintype "passive"))
    )
    (net (code "51") (name "Net-(R29-Pad1)") (class "Default")
      (node (ref "R29") (pin "1") (pinfunction "1_1") (pintype "passive"))
      (node (ref "U7") (pin "4") (pinfunction "4_4") (pintype "passive"))
    )
    (net (code "52") (name "Net-(U1A-BOOT0)") (class "Default")
      (node (ref "R17") (pin "1") (pinfunction "1_1") (pintype "passive"))
      (node (ref "U1") (pin "60") (pinfunction "BOOT0_60") (pintype "input"))
    )
    (net (code "53") (name "Net-(U1B-VSSA)") (class "Default")
      (node (ref "C12") (pin "2") (pinfunction "2_2") (pintype "passive"))
      (node (ref "C13") (pin "2") (pinfunction "2_2") (pintype "passive"))
      (node (ref "C14") (pin "2") (pinfunction "2_2") (pintype "passive"))
      (node (ref "C15") (pin "2") (pinfunction "2_2") (pintype "passive"))
      (node (ref "R18") (pin "2") (pinfunction "2_2") (pintype "passive"))
      (node (ref "U1") (pin "12") (pinfunction "VSSA_12") (pintype "power_in"))
      (node (ref "U1") (pin "18") (pinfunction "VSS_4_18") (pintype "power_in"))
      (node (ref "U1") (pin "31") (pinfunction "VSS_1_31") (pintype "power_in"))
      (node (ref "U1") (pin "47") (pinfunction "VSS_2_47") (pintype "power_in"))
      (node (ref "U1") (pin "63") (pinfunction "VSS_3_63") (pintype "power_in"))
    )
    (net (code "54") (name "Net-(U3-UART1_DTR)") (class "Default")
      (node (ref "R9") (pin "2") (pinfunction "2_2") (pintype "passive"))
      (node (ref "U3") (pin "6") (pinfunction "UART1_DTR_6") (pintype "passive"))
    )
    (net (code "55") (name "Net-(U4-ADJ)") (class "Default")
      (node (ref "R1") (pin "1") (pinfunction "1_1") (pintype "passive"))
      (node (ref "R2") (pin "1") (pinfunction "1_1") (pintype "passive"))
      (node (ref "U4") (pin "5") (pinfunction "ADJ_5") (pintype "passive"))
    )
    (net (code "56") (name "Net-(U5-GND)") (class "Default")
      (node (ref "R16") (pin "2") (pinfunction "2_2") (pintype "passive"))
      (node (ref "U5") (pin "2") (pinfunction "GND_2") (pintype "passive"))
    )
    (net (code "57") (name "Net-(U10-A0)") (class "Default")
      (node (ref "R40") (pin "2") (pinfunction "2_2") (pintype "passive"))
      (node (ref "U10") (pin "1") (pinfunction "A0_1") (pintype "input"))
      (node (ref "U10") (pin "2") (pinfunction "A1_2") (pintype "input"))
      (node (ref "U10") (pin "3") (pinfunction "A2_3") (pintype "input"))
      (node (ref "U10") (pin "7") (pinfunction "WP_7") (pintype "bidirectional"))
    )
    (net (code "58") (name "VCC3.3") (class "Default")
      (node (ref "C12") (pin "1") (pinfunction "1_1") (pintype "passive"))
      (node (ref "C13") (pin "1") (pinfunction "1_1") (pintype "passive"))
      (node (ref "C14") (pin "1") (pinfunction "1_1") (pintype "passive"))
      (node (ref "C15") (pin "1") (pinfunction "1_1") (pintype "passive"))
      (node (ref "C24") (pin "1") (pinfunction "1_1") (pintype "passive"))
      (node (ref "C25") (pin "2") (pinfunction "2_2") (pintype "passive"))
      (node (ref "D3") (pin "1") (pinfunction "1_1") (pintype "passive"))
      (node (ref "P1") (pin "3") (pinfunction "COM_3") (pintype "passive"))
      (node (ref "P2") (pin "3") (pinfunction "COM_3") (pintype "passive"))
      (node (ref "P3") (pin "1") (pinfunction "VCC_1") (pintype "passive"))
      (node (ref "P4") (pin "1") (pinfunction "1_1") (pintype "passive"))
      (node (ref "R19") (pin "1") (pinfunction "1_1") (pintype "passive"))
      (node (ref "R34") (pin "2") (pinfunction "2_2") (pintype "passive"))
      (node (ref "R35") (pin "2") (pinfunction "2_2") (pintype "passive"))
      (node (ref "R41") (pin "2") (pinfunction "2_2") (pintype "passive"))
      (node (ref "R42") (pin "2") (pinfunction "2_2") (pintype "passive"))
      (node (ref "R44") (pin "1") (pinfunction "1_1") (pintype "passive"))
      (node (ref "U1") (pin "13") (pinfunction "VDDA_13") (pintype "power_in"))
      (node (ref "U1") (pin "19") (pinfunction "VDD_4_19") (pintype "power_in"))
      (node (ref "U1") (pin "32") (pinfunction "VDD_1_32") (pintype "power_in"))
      (node (ref "U1") (pin "48") (pinfunction "VDD_2_48") (pintype "power_in"))
      (node (ref "U1") (pin "64") (pinfunction "VDD_3_64") (pintype "power_in"))
      (node (ref "U10") (pin "4") (pinfunction "Vss_4") (pintype "power_in"))
      (node (ref "U10") (pin "8") (pinfunction "Vcc_8") (pintype "power_in"))
      (node (ref "U8") (pin "2") (pinfunction "Vout_2") (pintype "passive"))
    )
    (net (code "59") (name "VCC4.16") (class "Default")
      (node (ref "C3") (pin "1") (pinfunction "1_1") (pintype "passive"))
      (node (ref "C4") (pin "1") (pinfunction "1_1") (pintype "passive"))
      (node (ref "D1") (pin "2") (pinfunction "2_2") (pintype "passive"))
      (node (ref "R1") (pin "2") (pinfunction "2_2") (pintype "passive"))
      (node (ref "U3") (pin "34") (pinfunction "VBAT_34") (pintype "passive"))
      (node (ref "U3") (pin "35") (pinfunction "VBAT_35") (pintype "passive"))
      (node (ref "U4") (pin "4") (pinfunction "OUT_4") (pintype "passive"))
    )
    (net (code "60") (name "VCC5") (class "Default")
      (node (ref "C28") (pin "1") (pinfunction "1_1") (pintype "passive"))
      (node (ref "C29") (pin "1") (pinfunction "1_1") (pintype "passive"))
      (node (ref "R10") (pin "2") (pinfunction "2_2") (pintype "passive"))
      (node (ref "R22") (pin "2") (pinfunction "2_2") (pintype "passive"))
      (node (ref "R28") (pin "2") (pinfunction "2_2") (pintype "passive"))
      (node (ref "R43") (pin "1") (pinfunction "1_1") (pintype "passive"))
      (node (ref "R45") (pin "1") (pinfunction "1_1") (pintype "passive"))
      (node (ref "U5") (pin "5") (pinfunction "REF_5") (pintype "passive"))
      (node (ref "U9") (pin "2") (pinfunction "Vout_2") (pintype "passive"))
    )
    (net (code "61") (name "VCC12v") (class "Default")
      (node (ref "C1") (pin "1") (pinfunction "1_1") (pintype "passive"))
      (node (ref "C2") (pin "2") (pinfunction "2_2") (pintype "passive"))
      (node (ref "C22") (pin "1") (pinfunction "1_1") (pintype "passive"))
      (node (ref "C23") (pin "2") (pinfunction "2_2") (pintype "passive"))
      (node (ref "C26") (pin "1") (pinfunction "1_1") (pintype "passive"))
      (node (ref "C27") (pin "2") (pinfunction "2_2") (pintype "passive"))
      (node (ref "C30") (pin "1") (pinfunction "1_1") (pintype "passive"))
      (node (ref "D4") (pin "2") (pinfunction "2_2") (pintype "passive"))
      (node (ref "D5") (pin "2") (pinfunction "2_2") (pintype "passive"))
      (node (ref "P1") (pin "1") (pinfunction "VCC_1") (pintype "passive"))
      (node (ref "P2") (pin "1") (pinfunction "VCC_1") (pintype "passive"))
      (node (ref "R24") (pin "2") (pinfunction "2_2") (pintype "passive"))
      (node (ref "R29") (pin "2") (pinfunction "2_2") (pintype "passive"))
      (node (ref "U4") (pin "1") (pinfunction "EN_1") (pintype "passive"))
      (node (ref "U4") (pin "2") (pinfunction "IN_2") (pintype "passive"))
      (node (ref "U8") (pin "3") (pinfunction "Vin_3") (pintype "power_in"))
      (node (ref "U9") (pin "3") (pinfunction "Vin_3") (pintype "power_in"))
      (node (ref "V1") (pin "1") (pinfunction "vcc_1") (pintype "passive"))
    )
    (net (code "62") (name "unconnected-(P1-NC-Pad4)") (class "Default")
      (node (ref "P1") (pin "4") (pinfunction "NC_4") (pintype "passive"))
    )
    (net (code "63") (name "unconnected-(P2-NC-Pad4)") (class "Default")
      (node (ref "P2") (pin "4") (pinfunction "NC_4") (pintype "passive"))
    )
    (net (code "64") (name "unconnected-(U1A-PA0-WKUP-Pad14)") (class "Default")
      (node (ref "U1") (pin "14") (pinfunction "PA0-WKUP_14") (pintype "bidirectional"))
    )
    (net (code "65") (name "unconnected-(U1A-PA2-Pad16)") (class "Default")
      (node (ref "U1") (pin "16") (pinfunction "PA2_16") (pintype "bidirectional"))
    )
    (net (code "66") (name "unconnected-(U1A-PA3-Pad17)") (class "Default")
      (node (ref "U1") (pin "17") (pinfunction "PA3_17") (pintype "bidirectional"))
    )
    (net (code "67") (name "unconnected-(U1A-PA4-Pad20)") (class "Default")
      (node (ref "U1") (pin "20") (pinfunction "PA4_20") (pintype "bidirectional"))
    )
    (net (code "68") (name "unconnected-(U1A-PA5-Pad21)") (class "Default")
      (node (ref "U1") (pin "21") (pinfunction "PA5_21") (pintype "bidirectional"))
    )
    (net (code "69") (name "unconnected-(U1A-PA6-Pad22)") (class "Default")
      (node (ref "U1") (pin "22") (pinfunction "PA6_22") (pintype "bidirectional"))
    )
    (net (code "70") (name "unconnected-(U1A-PA7-Pad23)") (class "Default")
      (node (ref "U1") (pin "23") (pinfunction "PA7_23") (pintype "bidirectional"))
    )
    (net (code "71") (name "unconnected-(U1A-PA8-Pad41)") (class "Default")
      (node (ref "U1") (pin "41") (pinfunction "PA8_41") (pintype "bidirectional"))
    )
    (net (code "72") (name "unconnected-(U1A-PA11-Pad44)") (class "Default")
      (node (ref "U1") (pin "44") (pinfunction "PA11_44") (pintype "bidirectional"))
    )
    (net (code "73") (name "unconnected-(U1A-PA12-Pad45)") (class "Default")
      (node (ref "U1") (pin "45") (pinfunction "PA12_45") (pintype "bidirectional"))
    )
    (net (code "74") (name "unconnected-(U1A-PA15-Pad50)") (class "Default")
      (node (ref "U1") (pin "50") (pinfunction "PA15_50") (pintype "bidirectional"))
    )
    (net (code "75") (name "unconnected-(U1A-PB0-Pad26)") (class "Default")
      (node (ref "U1") (pin "26") (pinfunction "PB0_26") (pintype "bidirectional"))
    )
    (net (code "76") (name "unconnected-(U1A-PB1-Pad27)") (class "Default")
      (node (ref "U1") (pin "27") (pinfunction "PB1_27") (pintype "bidirectional"))
    )
    (net (code "77") (name "unconnected-(U1A-PB2-Pad28)") (class "Default")
      (node (ref "U1") (pin "28") (pinfunction "PB2_28") (pintype "bidirectional"))
    )
    (net (code "78") (name "unconnected-(U1A-PB3-Pad55)") (class "Default")
      (node (ref "U1") (pin "55") (pinfunction "PB3_55") (pintype "bidirectional"))
    )
    (net (code "79") (name "unconnected-(U1A-PB4-Pad56)") (class "Default")
      (node (ref "U1") (pin "56") (pinfunction "PB4_56") (pintype "bidirectional"))
    )
    (net (code "80") (name "unconnected-(U1A-PB5-Pad57)") (class "Default")
      (node (ref "U1") (pin "57") (pinfunction "PB5_57") (pintype "bidirectional"))
    )
    (net (code "81") (name "unconnected-(U1A-PB6-Pad58)") (class "Default")
      (node (ref "U1") (pin "58") (pinfunction "PB6_58") (pintype "bidirectional"))
    )
    (net (code "82") (name "unconnected-(U1A-PB7-Pad59)") (class "Default")
      (node (ref "U1") (pin "59") (pinfunction "PB7_59") (pintype "bidirectional"))
    )
    (net (code "83") (name "unconnected-(U1A-PB8-Pad61)") (class "Default")
      (node (ref "U1") (pin "61") (pinfunction "PB8_61") (pintype "bidirectional"))
    )
    (net (code "84") (name "unconnected-(U1A-PB9-Pad62)") (class "Default")
      (node (ref "U1") (pin "62") (pinfunction "PB9_62") (pintype "bidirectional"))
    )
    (net (code "85") (name "unconnected-(U1A-PB13-Pad34)") (class "Default")
      (node (ref "U1") (pin "34") (pinfunction "PB13_34") (pintype "bidirectional"))
    )
    (net (code "86") (name "unconnected-(U1A-PB14-Pad35)") (class "Default")
      (node (ref "U1") (pin "35") (pinfunction "PB14_35") (pintype "bidirectional"))
    )
    (net (code "87") (name "unconnected-(U1A-PB15-Pad36)") (class "Default")
      (node (ref "U1") (pin "36") (pinfunction "PB15_36") (pintype "bidirectional"))
    )
    (net (code "88") (name "unconnected-(U1A-PC2-Pad10)") (class "Default")
      (node (ref "U1") (pin "10") (pinfunction "PC2_10") (pintype "bidirectional"))
    )
    (net (code "89") (name "unconnected-(U1A-PC3-Pad11)") (class "Default")
      (node (ref "U1") (pin "11") (pinfunction "PC3_11") (pintype "bidirectional"))
    )
    (net (code "90") (name "unconnected-(U1A-PC5-Pad25)") (class "Default")
      (node (ref "U1") (pin "25") (pinfunction "PC5_25") (pintype "bidirectional"))
    )
    (net (code "91") (name "unconnected-(U1A-PC6-Pad37)") (class "Default")
      (node (ref "U1") (pin "37") (pinfunction "PC6_37") (pintype "bidirectional"))
    )
    (net (code "92") (name "unconnected-(U1A-PC7-Pad38)") (class "Default")
      (node (ref "U1") (pin "38") (pinfunction "PC7_38") (pintype "bidirectional"))
    )
    (net (code "93") (name "unconnected-(U1A-PC10-Pad51)") (class "Default")
      (node (ref "U1") (pin "51") (pinfunction "PC10_51") (pintype "bidirectional"))
    )
    (net (code "94") (name "unconnected-(U1A-PC11-Pad52)") (class "Default")
      (node (ref "U1") (pin "52") (pinfunction "PC11_52") (pintype "bidirectional"))
    )
    (net (code "95") (name "unconnected-(U1A-PC12-Pad53)") (class "Default")
      (node (ref "U1") (pin "53") (pinfunction "PC12_53") (pintype "bidirectional"))
    )
    (net (code "96") (name "unconnected-(U1A-PC13-TAMPER-RTC-Pad2)") (class "Default")
      (node (ref "U1") (pin "2") (pinfunction "PC13-TAMPER-RTC_2") (pintype "bidirectional"))
    )
    (net (code "97") (name "unconnected-(U1A-PD2-Pad54)") (class "Default")
      (node (ref "U1") (pin "54") (pinfunction "PD2_54") (pintype "bidirectional"))
    )
    (net (code "98") (name "unconnected-(U3-ADC-Pad38)") (class "Default")
      (node (ref "U3") (pin "38") (pinfunction "ADC_38") (pintype "passive"))
    )
    (net (code "99") (name "unconnected-(U3-ANT-Pad32)") (class "Default")
      (node (ref "U3") (pin "32") (pinfunction "ANT_32") (pintype "passive"))
    )
    (net (code "100") (name "unconnected-(U3-CHG_DET-Pad24)") (class "Default")
      (node (ref "U3") (pin "24") (pinfunction "CHG_DET_24") (pintype "passive"))
    )
    (net (code "101") (name "unconnected-(U3-GPIO_6-Pad29)") (class "Default")
      (node (ref "U3") (pin "29") (pinfunction "GPIO_6_29") (pintype "passive"))
    )
    (net (code "102") (name "unconnected-(U3-HST_RXD-Pad25)") (class "Default")
      (node (ref "U3") (pin "25") (pinfunction "HST_RXD_25") (pintype "passive"))
    )
    (net (code "103") (name "unconnected-(U3-HST_TXD-Pad26)") (class "Default")
      (node (ref "U3") (pin "26") (pinfunction "HST_TXD_26") (pintype "passive"))
    )
    (net (code "104") (name "unconnected-(U3-MICN-Pad10)") (class "Default")
      (node (ref "U3") (pin "10") (pinfunction "MICN_10") (pintype "passive"))
    )
    (net (code "105") (name "unconnected-(U3-MICP-Pad9)") (class "Default")
      (node (ref "U3") (pin "9") (pinfunction "MICP_9") (pintype "passive"))
    )
    (net (code "106") (name "unconnected-(U3-SIM_DET-Pad14)") (class "Default")
      (node (ref "U3") (pin "14") (pinfunction "SIM_DET_14") (pintype "passive"))
    )
    (net (code "107") (name "unconnected-(U3-SPKN-Pad12)") (class "Default")
      (node (ref "U3") (pin "12") (pinfunction "SPKN_12") (pintype "passive"))
    )
    (net (code "108") (name "unconnected-(U3-SPKP-Pad11)") (class "Default")
      (node (ref "U3") (pin "11") (pinfunction "SPKP_11") (pintype "passive"))
    )
    (net (code "109") (name "unconnected-(U3-UART1_CTS-Pad4)") (class "Default")
      (node (ref "U3") (pin "4") (pinfunction "UART1_CTS_4") (pintype "passive"))
    )
    (net (code "110") (name "unconnected-(U3-UART1_DCD-Pad5)") (class "Default")
      (node (ref "U3") (pin "5") (pinfunction "UART1_DCD_5") (pintype "passive"))
    )
    (net (code "111") (name "unconnected-(U3-UART1_RI-Pad7)") (class "Default")
      (node (ref "U3") (pin "7") (pinfunction "UART1_RI_7") (pintype "passive"))
    )
    (net (code "112") (name "unconnected-(U3-UART1_RTS-Pad3)") (class "Default")
      (node (ref "U3") (pin "3") (pinfunction "UART1_RTS_3") (pintype "passive"))
    )
    (net (code "113") (name "unconnected-(U3-UART2_RXD-Pad23)") (class "Default")
      (node (ref "U3") (pin "23") (pinfunction "UART2_RXD_23") (pintype "passive"))
    )
    (net (code "114") (name "unconnected-(U3-UART2_TXD-Pad22)") (class "Default")
      (node (ref "U3") (pin "22") (pinfunction "UART2_TXD_22") (pintype "passive"))
    )
    (net (code "115") (name "unconnected-(U3-VRTC-Pad28)") (class "Default")
      (node (ref "U3") (pin "28") (pinfunction "VRTC_28") (pintype "passive"))
    )
  )
)
